# PROB_S7CAS_ADC.net
KiCad netlist of a schematic drawn in Altium Designer
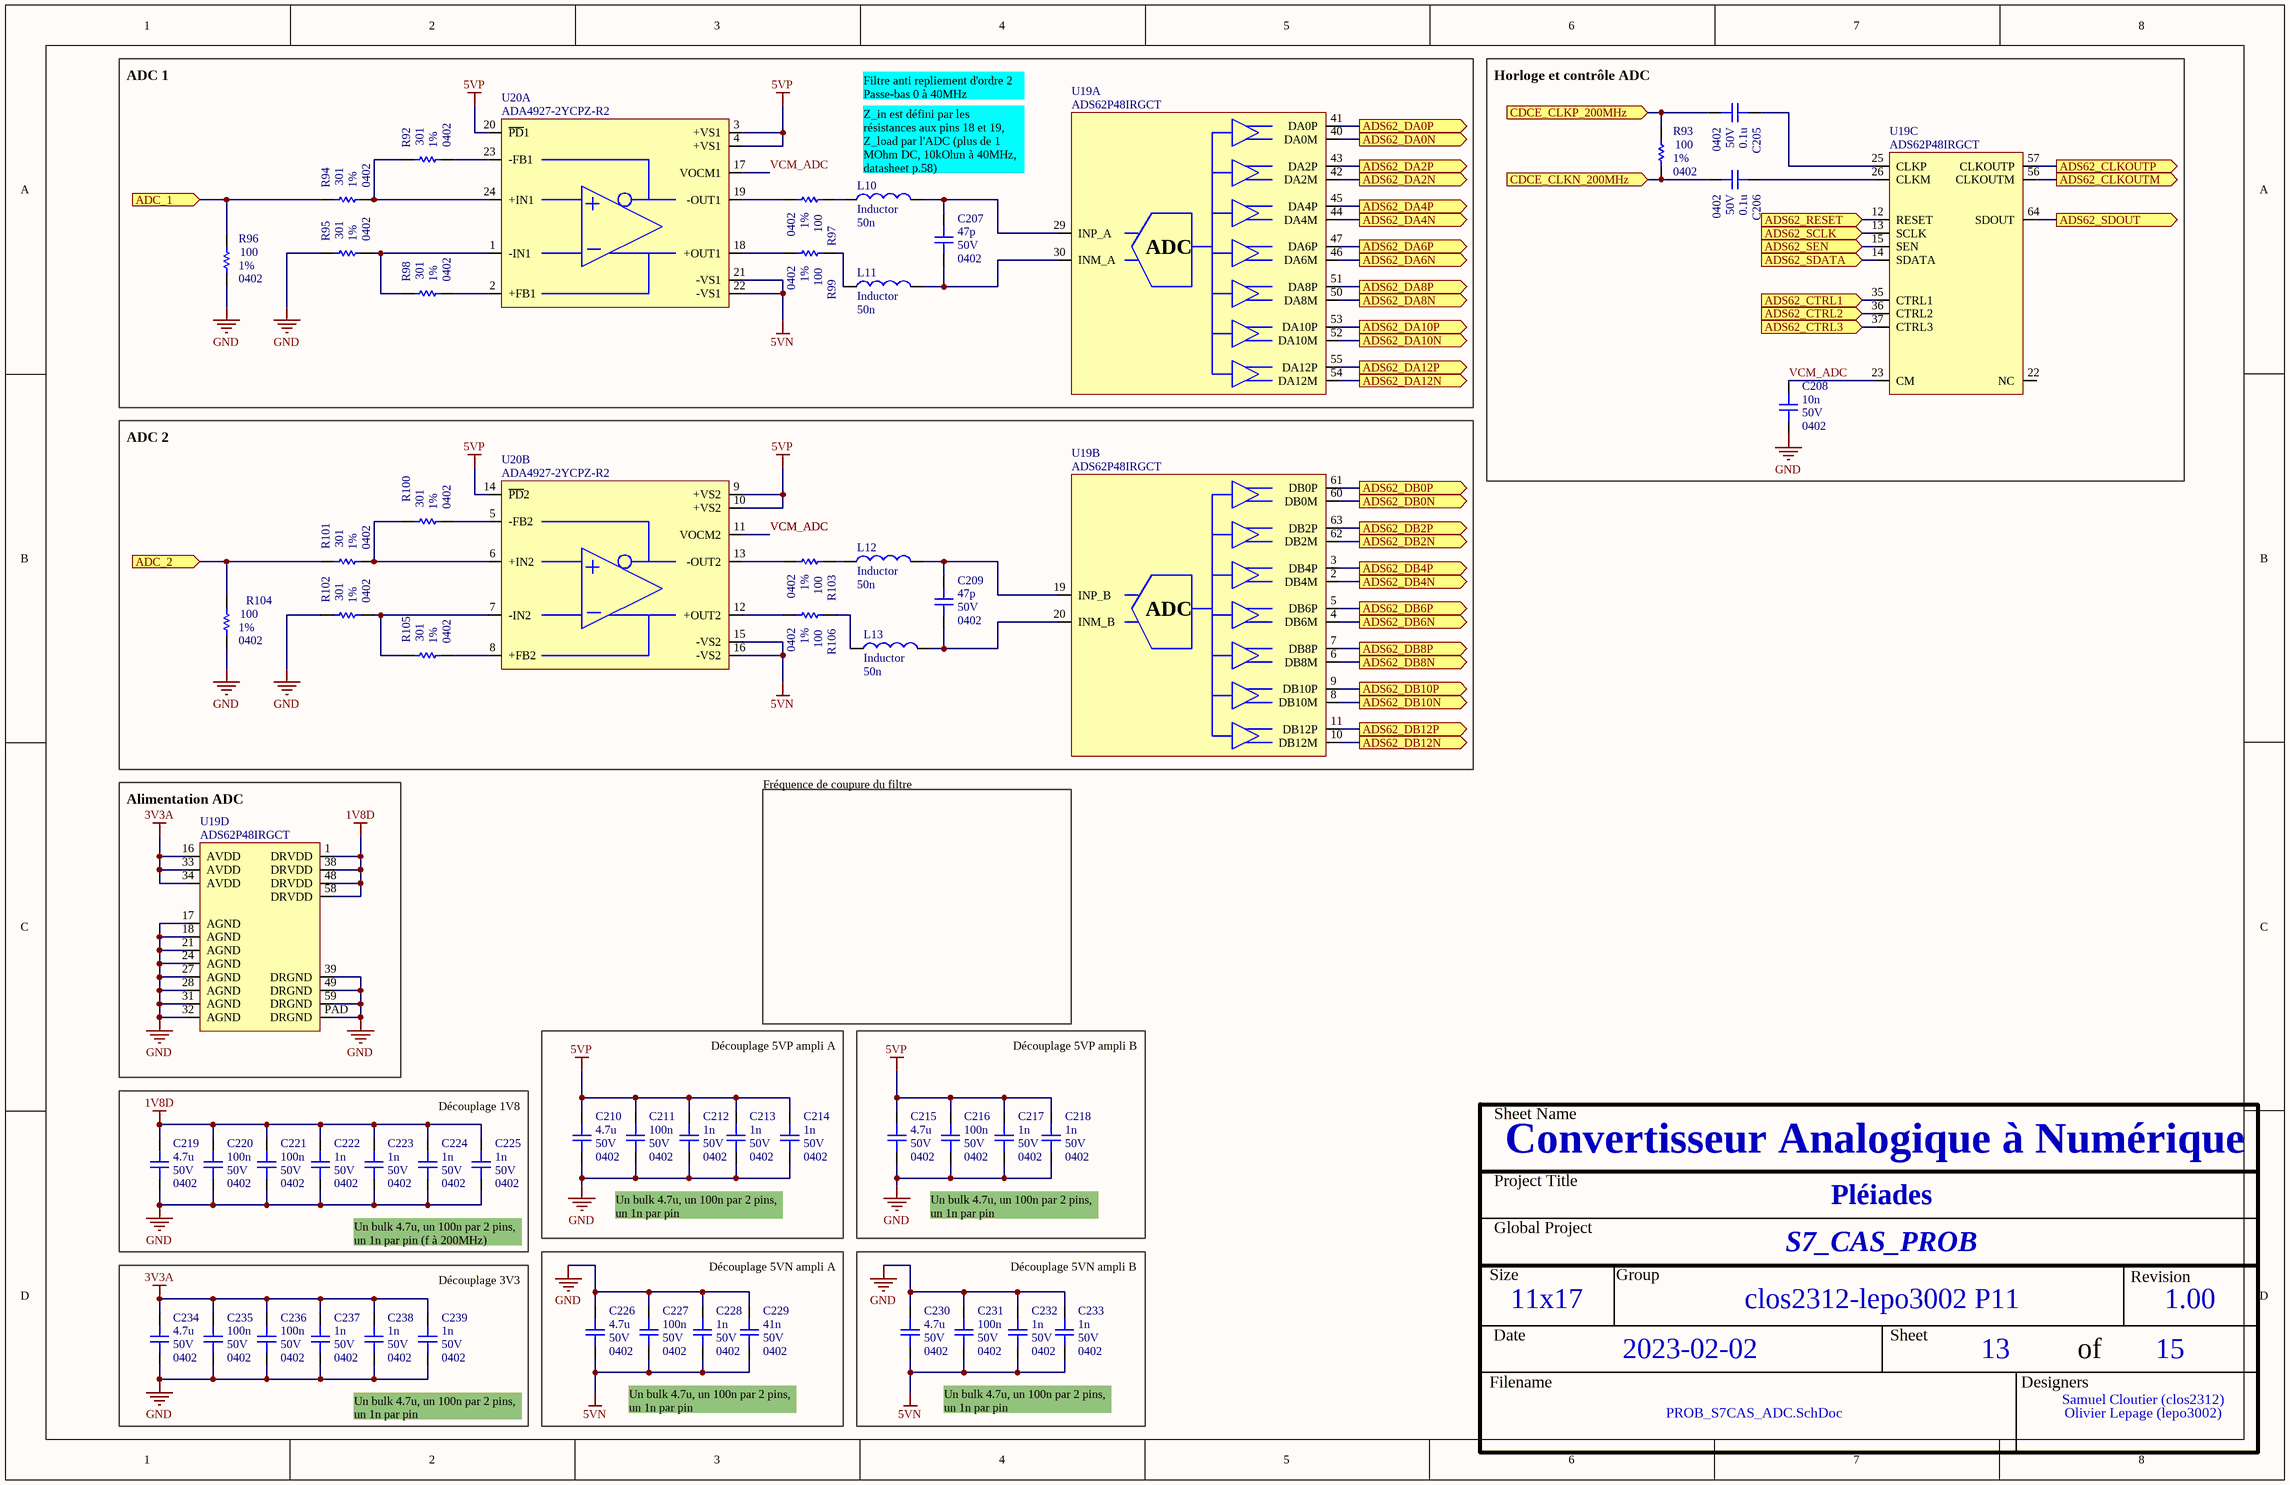
[diagram p0: PROB_S7CAS_ADC.SchDoc]

(export (version "E")
  (design (tool "Eeschema 10.0.6"))
  (components
    (comp (ref "C205")
      (value "0.1u")
      (footprint "CAP_0402")
      (description "CAP - 0402")
      (fields
        (field (name "VOLTAGE") "50V")
        (field (name "PACKAGE") "0402")
        (field (name "CREATEDBY") "Jonathan Bouchard")
      )
      (libsource (lib "S7CAS_LIB2021") (part "CAP - 0402"))
    )
    (comp (ref "C206")
      (value "0.1u")
      (footprint "CAP_0402")
      (description "CAP - 0402")
      (fields
        (field (name "VOLTAGE") "50V")
        (field (name "PACKAGE") "0402")
        (field (name "CREATEDBY") "Jonathan Bouchard")
      )
      (libsource (lib "S7CAS_LIB2021") (part "CAP - 0402"))
    )
    (comp (ref "C207")
      (value "47p")
      (footprint "CAP_0402")
      (description "CAP - 0402")
      (fields
        (field (name "VOLTAGE") "50V")
        (field (name "PACKAGE") "0402")
        (field (name "CREATEDBY") "Jonathan Bouchard")
      )
      (libsource (lib "S7CAS_LIB2021") (part "CAP - 0402"))
    )
    (comp (ref "C208")
      (value "10n")
      (footprint "CAP_0402")
      (description "CAP - 0402")
      (fields
        (field (name "VOLTAGE") "50V")
        (field (name "PACKAGE") "0402")
        (field (name "CREATEDBY") "Jonathan Bouchard")
      )
      (libsource (lib "S7CAS_LIB2021") (part "CAP - 0402"))
    )
    (comp (ref "C209")
      (value "47p")
      (footprint "CAP_0402")
      (description "CAP - 0402")
      (fields
        (field (name "VOLTAGE") "50V")
        (field (name "PACKAGE") "0402")
        (field (name "CREATEDBY") "Jonathan Bouchard")
      )
      (libsource (lib "S7CAS_LIB2021") (part "CAP - 0402"))
    )
    (comp (ref "C210")
      (value "4.7u")
      (footprint "CAP_0402")
      (description "CAP - 0402")
      (fields
        (field (name "VOLTAGE") "50V")
        (field (name "PACKAGE") "0402")
        (field (name "CREATEDBY") "Jonathan Bouchard")
      )
      (libsource (lib "S7CAS_LIB2021") (part "CAP - 0402"))
    )
    (comp (ref "C211")
      (value "100n")
      (footprint "CAP_0402")
      (description "CAP - 0402")
      (fields
        (field (name "VOLTAGE") "50V")
        (field (name "PACKAGE") "0402")
        (field (name "CREATEDBY") "Jonathan Bouchard")
      )
      (libsource (lib "S7CAS_LIB2021") (part "CAP - 0402"))
    )
    (comp (ref "C212")
      (value "1n")
      (footprint "CAP_0402")
      (description "CAP - 0402")
      (fields
        (field (name "VOLTAGE") "50V")
        (field (name "PACKAGE") "0402")
        (field (name "CREATEDBY") "Jonathan Bouchard")
      )
      (libsource (lib "S7CAS_LIB2021") (part "CAP - 0402"))
    )
    (comp (ref "C213")
      (value "1n")
      (footprint "CAP_0402")
      (description "CAP - 0402")
      (fields
        (field (name "VOLTAGE") "50V")
        (field (name "PACKAGE") "0402")
        (field (name "CREATEDBY") "Jonathan Bouchard")
      )
      (libsource (lib "S7CAS_LIB2021") (part "CAP - 0402"))
    )
    (comp (ref "C214")
      (value "1n")
      (footprint "CAP_0402")
      (description "CAP - 0402")
      (fields
        (field (name "VOLTAGE") "50V")
        (field (name "PACKAGE") "0402")
        (field (name "CREATEDBY") "Jonathan Bouchard")
      )
      (libsource (lib "S7CAS_LIB2021") (part "CAP - 0402"))
    )
    (comp (ref "C215")
      (value "4.7u")
      (footprint "CAP_0402")
      (description "CAP - 0402")
      (fields
        (field (name "VOLTAGE") "50V")
        (field (name "PACKAGE") "0402")
        (field (name "CREATEDBY") "Jonathan Bouchard")
      )
      (libsource (lib "S7CAS_LIB2021") (part "CAP - 0402"))
    )
    (comp (ref "C216")
      (value "100n")
      (footprint "CAP_0402")
      (description "CAP - 0402")
      (fields
        (field (name "VOLTAGE") "50V")
        (field (name "PACKAGE") "0402")
        (field (name "CREATEDBY") "Jonathan Bouchard")
      )
      (libsource (lib "S7CAS_LIB2021") (part "CAP - 0402"))
    )
    (comp (ref "C217")
      (value "1n")
      (footprint "CAP_0402")
      (description "CAP - 0402")
      (fields
        (field (name "VOLTAGE") "50V")
        (field (name "PACKAGE") "0402")
        (field (name "CREATEDBY") "Jonathan Bouchard")
      )
      (libsource (lib "S7CAS_LIB2021") (part "CAP - 0402"))
    )
    (comp (ref "C218")
      (value "1n")
      (footprint "CAP_0402")
      (description "CAP - 0402")
      (fields
        (field (name "VOLTAGE") "50V")
        (field (name "PACKAGE") "0402")
        (field (name "CREATEDBY") "Jonathan Bouchard")
      )
      (libsource (lib "S7CAS_LIB2021") (part "CAP - 0402"))
    )
    (comp (ref "C219")
      (value "4.7u")
      (footprint "CAP_0402")
      (description "CAP - 0402")
      (fields
        (field (name "VOLTAGE") "50V")
        (field (name "PACKAGE") "0402")
        (field (name "CREATEDBY") "Jonathan Bouchard")
      )
      (libsource (lib "S7CAS_LIB2021") (part "CAP - 0402"))
    )
    (comp (ref "C220")
      (value "100n")
      (footprint "CAP_0402")
      (description "CAP - 0402")
      (fields
        (field (name "VOLTAGE") "50V")
        (field (name "PACKAGE") "0402")
        (field (name "CREATEDBY") "Jonathan Bouchard")
      )
      (libsource (lib "S7CAS_LIB2021") (part "CAP - 0402"))
    )
    (comp (ref "C221")
      (value "100n")
      (footprint "CAP_0402")
      (description "CAP - 0402")
      (fields
        (field (name "VOLTAGE") "50V")
        (field (name "PACKAGE") "0402")
        (field (name "CREATEDBY") "Jonathan Bouchard")
      )
      (libsource (lib "S7CAS_LIB2021") (part "CAP - 0402"))
    )
    (comp (ref "C222")
      (value "1n")
      (footprint "CAP_0402")
      (description "CAP - 0402")
      (fields
        (field (name "VOLTAGE") "50V")
        (field (name "PACKAGE") "0402")
        (field (name "CREATEDBY") "Jonathan Bouchard")
      )
      (libsource (lib "S7CAS_LIB2021") (part "CAP - 0402"))
    )
    (comp (ref "C223")
      (value "1n")
      (footprint "CAP_0402")
      (description "CAP - 0402")
      (fields
        (field (name "VOLTAGE") "50V")
        (field (name "PACKAGE") "0402")
        (field (name "CREATEDBY") "Jonathan Bouchard")
      )
      (libsource (lib "S7CAS_LIB2021") (part "CAP - 0402"))
    )
    (comp (ref "C224")
      (value "1n")
      (footprint "CAP_0402")
      (description "CAP - 0402")
      (fields
        (field (name "VOLTAGE") "50V")
        (field (name "PACKAGE") "0402")
        (field (name "CREATEDBY") "Jonathan Bouchard")
      )
      (libsource (lib "S7CAS_LIB2021") (part "CAP - 0402"))
    )
    (comp (ref "C225")
      (value "1n")
      (footprint "CAP_0402")
      (description "CAP - 0402")
      (fields
        (field (name "VOLTAGE") "50V")
        (field (name "PACKAGE") "0402")
        (field (name "CREATEDBY") "Jonathan Bouchard")
      )
      (libsource (lib "S7CAS_LIB2021") (part "CAP - 0402"))
    )
    (comp (ref "C226")
      (value "4.7u")
      (footprint "CAP_0402")
      (description "CAP - 0402")
      (fields
        (field (name "VOLTAGE") "50V")
        (field (name "PACKAGE") "0402")
        (field (name "CREATEDBY") "Jonathan Bouchard")
      )
      (libsource (lib "S7CAS_LIB2021") (part "CAP - 0402"))
    )
    (comp (ref "C227")
      (value "100n")
      (footprint "CAP_0402")
      (description "CAP - 0402")
      (fields
        (field (name "VOLTAGE") "50V")
        (field (name "PACKAGE") "0402")
        (field (name "CREATEDBY") "Jonathan Bouchard")
      )
      (libsource (lib "S7CAS_LIB2021") (part "CAP - 0402"))
    )
    (comp (ref "C228")
      (value "1n")
      (footprint "CAP_0402")
      (description "CAP - 0402")
      (fields
        (field (name "VOLTAGE") "50V")
        (field (name "PACKAGE") "0402")
        (field (name "CREATEDBY") "Jonathan Bouchard")
      )
      (libsource (lib "S7CAS_LIB2021") (part "CAP - 0402"))
    )
    (comp (ref "C229")
      (value "41n")
      (footprint "CAP_0402")
      (description "CAP - 0402")
      (fields
        (field (name "VOLTAGE") "50V")
        (field (name "PACKAGE") "0402")
        (field (name "CREATEDBY") "Jonathan Bouchard")
      )
      (libsource (lib "S7CAS_LIB2021") (part "CAP - 0402"))
    )
    (comp (ref "C230")
      (value "4.7u")
      (footprint "CAP_0402")
      (description "CAP - 0402")
      (fields
        (field (name "VOLTAGE") "50V")
        (field (name "PACKAGE") "0402")
        (field (name "CREATEDBY") "Jonathan Bouchard")
      )
      (libsource (lib "S7CAS_LIB2021") (part "CAP - 0402"))
    )
    (comp (ref "C231")
      (value "100n")
      (footprint "CAP_0402")
      (description "CAP - 0402")
      (fields
        (field (name "VOLTAGE") "50V")
        (field (name "PACKAGE") "0402")
        (field (name "CREATEDBY") "Jonathan Bouchard")
      )
      (libsource (lib "S7CAS_LIB2021") (part "CAP - 0402"))
    )
    (comp (ref "C232")
      (value "1n")
      (footprint "CAP_0402")
      (description "CAP - 0402")
      (fields
        (field (name "VOLTAGE") "50V")
        (field (name "PACKAGE") "0402")
        (field (name "CREATEDBY") "Jonathan Bouchard")
      )
      (libsource (lib "S7CAS_LIB2021") (part "CAP - 0402"))
    )
    (comp (ref "C233")
      (value "1n")
      (footprint "CAP_0402")
      (description "CAP - 0402")
      (fields
        (field (name "VOLTAGE") "50V")
        (field (name "PACKAGE") "0402")
        (field (name "CREATEDBY") "Jonathan Bouchard")
      )
      (libsource (lib "S7CAS_LIB2021") (part "CAP - 0402"))
    )
    (comp (ref "C234")
      (value "4.7u")
      (footprint "CAP_0402")
      (description "CAP - 0402")
      (fields
        (field (name "VOLTAGE") "50V")
        (field (name "PACKAGE") "0402")
        (field (name "CREATEDBY") "Jonathan Bouchard")
      )
      (libsource (lib "S7CAS_LIB2021") (part "CAP - 0402"))
    )
    (comp (ref "C235")
      (value "100n")
      (footprint "CAP_0402")
      (description "CAP - 0402")
      (fields
        (field (name "VOLTAGE") "50V")
        (field (name "PACKAGE") "0402")
        (field (name "CREATEDBY") "Jonathan Bouchard")
      )
      (libsource (lib "S7CAS_LIB2021") (part "CAP - 0402"))
    )
    (comp (ref "C236")
      (value "100n")
      (footprint "CAP_0402")
      (description "CAP - 0402")
      (fields
        (field (name "VOLTAGE") "50V")
        (field (name "PACKAGE") "0402")
        (field (name "CREATEDBY") "Jonathan Bouchard")
      )
      (libsource (lib "S7CAS_LIB2021") (part "CAP - 0402"))
    )
    (comp (ref "C237")
      (value "1n")
      (footprint "CAP_0402")
      (description "CAP - 0402")
      (fields
        (field (name "VOLTAGE") "50V")
        (field (name "PACKAGE") "0402")
        (field (name "CREATEDBY") "Jonathan Bouchard")
      )
      (libsource (lib "S7CAS_LIB2021") (part "CAP - 0402"))
    )
    (comp (ref "C238")
      (value "1n")
      (footprint "CAP_0402")
      (description "CAP - 0402")
      (fields
        (field (name "VOLTAGE") "50V")
        (field (name "PACKAGE") "0402")
        (field (name "CREATEDBY") "Jonathan Bouchard")
      )
      (libsource (lib "S7CAS_LIB2021") (part "CAP - 0402"))
    )
    (comp (ref "C239")
      (value "1n")
      (footprint "CAP_0402")
      (description "CAP - 0402")
      (fields
        (field (name "VOLTAGE") "50V")
        (field (name "PACKAGE") "0402")
        (field (name "CREATEDBY") "Jonathan Bouchard")
      )
      (libsource (lib "S7CAS_LIB2021") (part "CAP - 0402"))
    )
    (comp (ref "L10")
      (value "Inductor")
      (footprint "INDM5250X66N")
      (description "IND PWR BEAD 50NH 48A SMD")
      (fields (field (name "ALTIUM_VALUE") "50n"))
      (libsource (lib "LIB_TEMP_S7CAS_SCH") (part "Inductor"))
    )
    (comp (ref "L11")
      (value "Inductor")
      (footprint "INDM5250X66N")
      (description "IND PWR BEAD 50NH 48A SMD")
      (fields (field (name "ALTIUM_VALUE") "50n"))
      (libsource (lib "LIB_TEMP_S7CAS_SCH") (part "Inductor"))
    )
    (comp (ref "L12")
      (value "Inductor")
      (footprint "INDM5250X66N")
      (description "IND PWR BEAD 50NH 48A SMD")
      (fields (field (name "ALTIUM_VALUE") "50n"))
      (libsource (lib "LIB_TEMP_S7CAS_SCH") (part "Inductor"))
    )
    (comp (ref "L13")
      (value "Inductor")
      (footprint "INDM5250X66N")
      (description "IND PWR BEAD 50NH 48A SMD")
      (fields (field (name "ALTIUM_VALUE") "50n"))
      (libsource (lib "LIB_TEMP_S7CAS_SCH") (part "Inductor"))
    )
    (comp (ref "R92")
      (value "301")
      (footprint "RES_0402")
      (description "RES - 0402")
      (fields
        (field (name "VOLTAGE") "50V")
        (field (name "POWER") "1/16W")
        (field (name "PACKAGE") "0402")
        (field (name "PRECISION") "1%")
        (field (name "CREATEDBY") "Jonathan Bouchard")
      )
      (libsource (lib "S7CAS_LIB2021") (part "RES - 0402"))
    )
    (comp (ref "R93")
      (value "100")
      (footprint "RES_0402")
      (description "RES - 0402")
      (fields
        (field (name "VOLTAGE") "50V")
        (field (name "POWER") "1/16W")
        (field (name "PACKAGE") "0402")
        (field (name "PRECISION") "1%")
        (field (name "CREATEDBY") "Jonathan Bouchard")
      )
      (libsource (lib "S7CAS_LIB2021") (part "RES - 0402"))
    )
    (comp (ref "R94")
      (value "301")
      (footprint "RES_0402")
      (description "RES - 0402")
      (fields
        (field (name "VOLTAGE") "50V")
        (field (name "POWER") "1/16W")
        (field (name "PACKAGE") "0402")
        (field (name "PRECISION") "1%")
        (field (name "CREATEDBY") "Jonathan Bouchard")
      )
      (libsource (lib "S7CAS_LIB2021") (part "RES - 0402"))
    )
    (comp (ref "R95")
      (value "301")
      (footprint "RES_0402")
      (description "RES - 0402")
      (fields
        (field (name "VOLTAGE") "50V")
        (field (name "POWER") "1/16W")
        (field (name "PACKAGE") "0402")
        (field (name "PRECISION") "1%")
        (field (name "CREATEDBY") "Jonathan Bouchard")
      )
      (libsource (lib "S7CAS_LIB2021") (part "RES - 0402"))
    )
    (comp (ref "R96")
      (value "100")
      (footprint "RES_0402")
      (description "RES - 0402")
      (fields
        (field (name "VOLTAGE") "50V")
        (field (name "POWER") "1/16W")
        (field (name "PACKAGE") "0402")
        (field (name "PRECISION") "1%")
        (field (name "CREATEDBY") "Jonathan Bouchard")
      )
      (libsource (lib "S7CAS_LIB2021") (part "RES - 0402"))
    )
    (comp (ref "R97")
      (value "100")
      (footprint "RES_0402")
      (description "RES - 0402")
      (fields
        (field (name "VOLTAGE") "50V")
        (field (name "POWER") "1/16W")
        (field (name "PACKAGE") "0402")
        (field (name "PRECISION") "1%")
        (field (name "CREATEDBY") "Jonathan Bouchard")
      )
      (libsource (lib "S7CAS_LIB2021") (part "RES - 0402"))
    )
    (comp (ref "R98")
      (value "301")
      (footprint "RES_0402")
      (description "RES - 0402")
      (fields
        (field (name "VOLTAGE") "50V")
        (field (name "POWER") "1/16W")
        (field (name "PACKAGE") "0402")
        (field (name "PRECISION") "1%")
        (field (name "CREATEDBY") "Jonathan Bouchard")
      )
      (libsource (lib "S7CAS_LIB2021") (part "RES - 0402"))
    )
    (comp (ref "R99")
      (value "100")
      (footprint "RES_0402")
      (description "RES - 0402")
      (fields
        (field (name "VOLTAGE") "50V")
        (field (name "POWER") "1/16W")
        (field (name "PACKAGE") "0402")
        (field (name "PRECISION") "1%")
        (field (name "CREATEDBY") "Jonathan Bouchard")
      )
      (libsource (lib "S7CAS_LIB2021") (part "RES - 0402"))
    )
    (comp (ref "R100")
      (value "301")
      (footprint "RES_0402")
      (description "RES - 0402")
      (fields
        (field (name "VOLTAGE") "50V")
        (field (name "POWER") "1/16W")
        (field (name "PACKAGE") "0402")
        (field (name "PRECISION") "1%")
        (field (name "CREATEDBY") "Jonathan Bouchard")
      )
      (libsource (lib "S7CAS_LIB2021") (part "RES - 0402"))
    )
    (comp (ref "R101")
      (value "301")
      (footprint "RES_0402")
      (description "RES - 0402")
      (fields
        (field (name "VOLTAGE") "50V")
        (field (name "POWER") "1/16W")
        (field (name "PACKAGE") "0402")
        (field (name "PRECISION") "1%")
        (field (name "CREATEDBY") "Jonathan Bouchard")
      )
      (libsource (lib "S7CAS_LIB2021") (part "RES - 0402"))
    )
    (comp (ref "R102")
      (value "301")
      (footprint "RES_0402")
      (description "RES - 0402")
      (fields
        (field (name "VOLTAGE") "50V")
        (field (name "POWER") "1/16W")
        (field (name "PACKAGE") "0402")
        (field (name "PRECISION") "1%")
        (field (name "CREATEDBY") "Jonathan Bouchard")
      )
      (libsource (lib "S7CAS_LIB2021") (part "RES - 0402"))
    )
    (comp (ref "R103")
      (value "100")
      (footprint "RES_0402")
      (description "RES - 0402")
      (fields
        (field (name "VOLTAGE") "50V")
        (field (name "POWER") "1/16W")
        (field (name "PACKAGE") "0402")
        (field (name "PRECISION") "1%")
        (field (name "CREATEDBY") "Jonathan Bouchard")
      )
      (libsource (lib "S7CAS_LIB2021") (part "RES - 0402"))
    )
    (comp (ref "R104")
      (value "100")
      (footprint "RES_0402")
      (description "RES - 0402")
      (fields
        (field (name "VOLTAGE") "50V")
        (field (name "POWER") "1/16W")
        (field (name "PACKAGE") "0402")
        (field (name "PRECISION") "1%")
        (field (name "CREATEDBY") "Jonathan Bouchard")
      )
      (libsource (lib "S7CAS_LIB2021") (part "RES - 0402"))
    )
    (comp (ref "R105")
      (value "301")
      (footprint "RES_0402")
      (description "RES - 0402")
      (fields
        (field (name "VOLTAGE") "50V")
        (field (name "POWER") "1/16W")
        (field (name "PACKAGE") "0402")
        (field (name "PRECISION") "1%")
        (field (name "CREATEDBY") "Jonathan Bouchard")
      )
      (libsource (lib "S7CAS_LIB2021") (part "RES - 0402"))
    )
    (comp (ref "R106")
      (value "100")
      (footprint "RES_0402")
      (description "RES - 0402")
      (fields
        (field (name "VOLTAGE") "50V")
        (field (name "POWER") "1/16W")
        (field (name "PACKAGE") "0402")
        (field (name "PRECISION") "1%")
        (field (name "CREATEDBY") "Jonathan Bouchard")
      )
      (libsource (lib "S7CAS_LIB2021") (part "RES - 0402"))
    )
    (comp (ref "U19")
      (value "ADS62P48IRGCT")
      (footprint "ADC_ADS62P48IRGCT")
      (description "ADC - 14 BIT 210MSPS SUAL - VQFN-64")
      (fields
        (field (name "VOLTAGE") "3.15 V ~ 3.6 V / 1.7 V ~ 1.9 V")
        (field (name "MFG") "Texas Instruments")
        (field (name "CREATEDBY") "Jonathan Bouchard")
      )
      (libsource (lib "S7CAS_LIB2021") (part "ADC_ADS62P48IRGCT"))
    )
    (comp (ref "U20")
      (value "ADA4927-2YCPZ-R2")
      (footprint "OPAMP_ADA4927-2YCPZ-R2")
      (description "OPAMP - CFA 2.3GHZ - QFN-24")
      (fields
        (field (name "VOLTAGE") "4.5 V ~ 11 V, ±2.25 V ~ 5.5 V")
        (field (name "MFG") "Analog Devices")
        (field (name "CREATEDBY") "Jonathan Bouchard")
      )
      (libsource (lib "S7CAS_LIB2021") (part "OPAMP_ADA4927-2YCPZ-R2"))
    )
  )
  (nets
    (net (code "1") (name "/ADC_1") (class "Default")
      (node (ref "R94") (pin "2") (pinfunction "2_2") (pintype "passive"))
      (node (ref "R96") (pin "2") (pinfunction "2_2") (pintype "passive"))
    )
    (net (code "2") (name "/ADC_2") (class "Default")
      (node (ref "R101") (pin "2") (pinfunction "2_2") (pintype "passive"))
      (node (ref "R104") (pin "2") (pinfunction "2_2") (pintype "passive"))
    )
    (net (code "3") (name "/ADS62_CLKOUTM") (class "Default")
      (node (ref "U19") (pin "56") (pinfunction "CLKOUTM_56") (pintype "passive"))
    )
    (net (code "4") (name "/ADS62_CLKOUTP") (class "Default")
      (node (ref "U19") (pin "57") (pinfunction "CLKOUTP_57") (pintype "passive"))
    )
    (net (code "5") (name "/ADS62_CTRL1") (class "Default")
      (node (ref "U19") (pin "35") (pinfunction "CTRL1_35") (pintype "passive"))
    )
    (net (code "6") (name "/ADS62_CTRL2") (class "Default")
      (node (ref "U19") (pin "36") (pinfunction "CTRL2_36") (pintype "passive"))
    )
    (net (code "7") (name "/ADS62_CTRL3") (class "Default")
      (node (ref "U19") (pin "37") (pinfunction "CTRL3_37") (pintype "passive"))
    )
    (net (code "8") (name "/ADS62_DA0N") (class "Default")
      (node (ref "U19") (pin "40") (pinfunction "DA0M_40") (pintype "passive"))
    )
    (net (code "9") (name "/ADS62_DA0P") (class "Default")
      (node (ref "U19") (pin "41") (pinfunction "DA0P_41") (pintype "passive"))
    )
    (net (code "10") (name "/ADS62_DA2N") (class "Default")
      (node (ref "U19") (pin "42") (pinfunction "DA2M_42") (pintype "passive"))
    )
    (net (code "11") (name "/ADS62_DA2P") (class "Default")
      (node (ref "U19") (pin "43") (pinfunction "DA2P_43") (pintype "passive"))
    )
    (net (code "12") (name "/ADS62_DA4N") (class "Default")
      (node (ref "U19") (pin "44") (pinfunction "DA4M_44") (pintype "passive"))
    )
    (net (code "13") (name "/ADS62_DA4P") (class "Default")
      (node (ref "U19") (pin "45") (pinfunction "DA4P_45") (pintype "passive"))
    )
    (net (code "14") (name "/ADS62_DA6N") (class "Default")
      (node (ref "U19") (pin "46") (pinfunction "DA6M_46") (pintype "passive"))
    )
    (net (code "15") (name "/ADS62_DA6P") (class "Default")
      (node (ref "U19") (pin "47") (pinfunction "DA6P_47") (pintype "passive"))
    )
    (net (code "16") (name "/ADS62_DA8N") (class "Default")
      (node (ref "U19") (pin "50") (pinfunction "DA8M_50") (pintype "passive"))
    )
    (net (code "17") (name "/ADS62_DA8P") (class "Default")
      (node (ref "U19") (pin "51") (pinfunction "DA8P_51") (pintype "passive"))
    )
    (net (code "18") (name "/ADS62_DA10N") (class "Default")
      (node (ref "U19") (pin "52") (pinfunction "DA10M_52") (pintype "passive"))
    )
    (net (code "19") (name "/ADS62_DA10P") (class "Default")
      (node (ref "U19") (pin "53") (pinfunction "DA10P_53") (pintype "passive"))
    )
    (net (code "20") (name "/ADS62_DA12N") (class "Default")
      (node (ref "U19") (pin "54") (pinfunction "DA12M_54") (pintype "passive"))
    )
    (net (code "21") (name "/ADS62_DA12P") (class "Default")
      (node (ref "U19") (pin "55") (pinfunction "DA12P_55") (pintype "passive"))
    )
    (net (code "22") (name "/ADS62_DB0N") (class "Default")
      (node (ref "U19") (pin "60") (pinfunction "DB0M_60") (pintype "passive"))
    )
    (net (code "23") (name "/ADS62_DB0P") (class "Default")
      (node (ref "U19") (pin "61") (pinfunction "DB0P_61") (pintype "passive"))
    )
    (net (code "24") (name "/ADS62_DB2N") (class "Default")
      (node (ref "U19") (pin "62") (pinfunction "DB2M_62") (pintype "passive"))
    )
    (net (code "25") (name "/ADS62_DB2P") (class "Default")
      (node (ref "U19") (pin "63") (pinfunction "DB2P_63") (pintype "passive"))
    )
    (net (code "26") (name "/ADS62_DB4N") (class "Default")
      (node (ref "U19") (pin "2") (pinfunction "DB4M_2") (pintype "passive"))
    )
    (net (code "27") (name "/ADS62_DB4P") (class "Default")
      (node (ref "U19") (pin "3") (pinfunction "DB4P_3") (pintype "passive"))
    )
    (net (code "28") (name "/ADS62_DB6N") (class "Default")
      (node (ref "U19") (pin "4") (pinfunction "DB6M_4") (pintype "passive"))
    )
    (net (code "29") (name "/ADS62_DB6P") (class "Default")
      (node (ref "U19") (pin "5") (pinfunction "DB6P_5") (pintype "passive"))
    )
    (net (code "30") (name "/ADS62_DB8N") (class "Default")
      (node (ref "U19") (pin "6") (pinfunction "DB8M_6") (pintype "passive"))
    )
    (net (code "31") (name "/ADS62_DB8P") (class "Default")
      (node (ref "U19") (pin "7") (pinfunction "DB8P_7") (pintype "passive"))
    )
    (net (code "32") (name "/ADS62_DB10N") (class "Default")
      (node (ref "U19") (pin "8") (pinfunction "DB10M_8") (pintype "passive"))
    )
    (net (code "33") (name "/ADS62_DB10P") (class "Default")
      (node (ref "U19") (pin "9") (pinfunction "DB10P_9") (pintype "passive"))
    )
    (net (code "34") (name "/ADS62_DB12N") (class "Default")
      (node (ref "U19") (pin "10") (pinfunction "DB12M_10") (pintype "passive"))
    )
    (net (code "35") (name "/ADS62_DB12P") (class "Default")
      (node (ref "U19") (pin "11") (pinfunction "DB12P_11") (pintype "passive"))
    )
    (net (code "36") (name "/ADS62_RESET") (class "Default")
      (node (ref "U19") (pin "12") (pinfunction "RESET_12") (pintype "passive"))
    )
    (net (code "37") (name "/ADS62_SCLK") (class "Default")
      (node (ref "U19") (pin "13") (pinfunction "SCLK_13") (pintype "passive"))
    )
    (net (code "38") (name "/ADS62_SDATA") (class "Default")
      (node (ref "U19") (pin "14") (pinfunction "SDATA_14") (pintype "passive"))
    )
    (net (code "39") (name "/ADS62_SDOUT") (class "Default")
      (node (ref "U19") (pin "64") (pinfunction "SDOUT_64") (pintype "passive"))
    )
    (net (code "40") (name "/ADS62_SEN") (class "Default")
      (node (ref "U19") (pin "15") (pinfunction "SEN_15") (pintype "passive"))
    )
    (net (code "41") (name "/CDCE_CLKN_200MHz") (class "Default")
      (node (ref "C206") (pin "1") (pinfunction "1_1") (pintype "passive"))
      (node (ref "R93") (pin "1") (pinfunction "1_1") (pintype "passive"))
    )
    (net (code "42") (name "/CDCE_CLKP_200MHz") (class "Default")
      (node (ref "C205") (pin "1") (pinfunction "1_1") (pintype "passive"))
      (node (ref "R93") (pin "2") (pinfunction "2_2") (pintype "passive"))
    )
    (net (code "43") (name "/VCM_ADC") (class "Default")
      (node (ref "C208") (pin "2") (pinfunction "2_2") (pintype "passive"))
      (node (ref "U19") (pin "23") (pinfunction "CM_23") (pintype "passive"))
      (node (ref "U20") (pin "11") (pinfunction "VOCM2_11") (pintype "passive"))
      (node (ref "U20") (pin "17") (pinfunction "VOCM1_17") (pintype "passive"))
    )
    (net (code "44") (name "1V8D") (class "Default")
      (node (ref "C219") (pin "2") (pinfunction "2_2") (pintype "passive"))
      (node (ref "C220") (pin "2") (pinfunction "2_2") (pintype "passive"))
      (node (ref "C221") (pin "2") (pinfunction "2_2") (pintype "passive"))
      (node (ref "C222") (pin "2") (pinfunction "2_2") (pintype "passive"))
      (node (ref "C223") (pin "2") (pinfunction "2_2") (pintype "passive"))
      (node (ref "C224") (pin "2") (pinfunction "2_2") (pintype "passive"))
      (node (ref "C225") (pin "2") (pinfunction "2_2") (pintype "passive"))
      (node (ref "U19") (pin "1") (pinfunction "DRVDD_1") (pintype "passive"))
      (node (ref "U19") (pin "38") (pinfunction "DRVDD_38") (pintype "passive"))
      (node (ref "U19") (pin "48") (pinfunction "DRVDD_48") (pintype "passive"))
      (node (ref "U19") (pin "58") (pinfunction "DRVDD_58") (pintype "passive"))
    )
    (net (code "45") (name "3V3A") (class "Default")
      (node (ref "C234") (pin "2") (pinfunction "2_2") (pintype "passive"))
      (node (ref "C235") (pin "2") (pinfunction "2_2") (pintype "passive"))
      (node (ref "C236") (pin "2") (pinfunction "2_2") (pintype "passive"))
      (node (ref "C237") (pin "2") (pinfunction "2_2") (pintype "passive"))
      (node (ref "C238") (pin "2") (pinfunction "2_2") (pintype "passive"))
      (node (ref "C239") (pin "2") (pinfunction "2_2") (pintype "passive"))
      (node (ref "U19") (pin "16") (pinfunction "AVDD_16") (pintype "passive"))
      (node (ref "U19") (pin "33") (pinfunction "AVDD_33") (pintype "passive"))
      (node (ref "U19") (pin "34") (pinfunction "AVDD_34") (pintype "passive"))
    )
    (net (code "46") (name "5VN") (class "Default")
      (node (ref "C226") (pin "1") (pinfunction "1_1") (pintype "passive"))
      (node (ref "C227") (pin "1") (pinfunction "1_1") (pintype "passive"))
      (node (ref "C228") (pin "1") (pinfunction "1_1") (pintype "passive"))
      (node (ref "C229") (pin "1") (pinfunction "1_1") (pintype "passive"))
      (node (ref "C230") (pin "1") (pinfunction "1_1") (pintype "passive"))
      (node (ref "C231") (pin "1") (pinfunction "1_1") (pintype "passive"))
      (node (ref "C232") (pin "1") (pinfunction "1_1") (pintype "passive"))
      (node (ref "C233") (pin "1") (pinfunction "1_1") (pintype "passive"))
      (node (ref "U20") (pin "15") (pinfunction "-VS2_15") (pintype "passive"))
      (node (ref "U20") (pin "16") (pinfunction "-VS2_16") (pintype "passive"))
      (node (ref "U20") (pin "21") (pinfunction "-VS1_21") (pintype "passive"))
      (node (ref "U20") (pin "22") (pinfunction "-VS1_22") (pintype "passive"))
    )
    (net (code "47") (name "5VP") (class "Default")
      (node (ref "C210") (pin "2") (pinfunction "2_2") (pintype "passive"))
      (node (ref "C211") (pin "2") (pinfunction "2_2") (pintype "passive"))
      (node (ref "C212") (pin "2") (pinfunction "2_2") (pintype "passive"))
      (node (ref "C213") (pin "2") (pinfunction "2_2") (pintype "passive"))
      (node (ref "C214") (pin "2") (pinfunction "2_2") (pintype "passive"))
      (node (ref "C215") (pin "2") (pinfunction "2_2") (pintype "passive"))
      (node (ref "C216") (pin "2") (pinfunction "2_2") (pintype "passive"))
      (node (ref "C217") (pin "2") (pinfunction "2_2") (pintype "passive"))
      (node (ref "C218") (pin "2") (pinfunction "2_2") (pintype "passive"))
      (node (ref "U20") (pin "10") (pinfunction "+VS2_10") (pintype "passive"))
      (node (ref "U20") (pin "14") (pinfunction "~{PD}2_14") (pintype "passive"))
      (node (ref "U20") (pin "20") (pinfunction "~{PD}1_20") (pintype "passive"))
      (node (ref "U20") (pin "3") (pinfunction "+VS1_3") (pintype "passive"))
      (node (ref "U20") (pin "4") (pinfunction "+VS1_4") (pintype "passive"))
      (node (ref "U20") (pin "9") (pinfunction "+VS2_9") (pintype "passive"))
    )
    (net (code "48") (name "GND") (class "Default")
      (node (ref "C208") (pin "1") (pinfunction "1_1") (pintype "passive"))
      (node (ref "C210") (pin "1") (pinfunction "1_1") (pintype "passive"))
      (node (ref "C211") (pin "1") (pinfunction "1_1") (pintype "passive"))
      (node (ref "C212") (pin "1") (pinfunction "1_1") (pintype "passive"))
      (node (ref "C213") (pin "1") (pinfunction "1_1") (pintype "passive"))
      (node (ref "C214") (pin "1") (pinfunction "1_1") (pintype "passive"))
      (node (ref "C215") (pin "1") (pinfunction "1_1") (pintype "passive"))
      (node (ref "C216") (pin "1") (pinfunction "1_1") (pintype "passive"))
      (node (ref "C217") (pin "1") (pinfunction "1_1") (pintype "passive"))
      (node (ref "C218") (pin "1") (pinfunction "1_1") (pintype "passive"))
      (node (ref "C219") (pin "1") (pinfunction "1_1") (pintype "passive"))
      (node (ref "C220") (pin "1") (pinfunction "1_1") (pintype "passive"))
      (node (ref "C221") (pin "1") (pinfunction "1_1") (pintype "passive"))
      (node (ref "C222") (pin "1") (pinfunction "1_1") (pintype "passive"))
      (node (ref "C223") (pin "1") (pinfunction "1_1") (pintype "passive"))
      (node (ref "C224") (pin "1") (pinfunction "1_1") (pintype "passive"))
      (node (ref "C225") (pin "1") (pinfunction "1_1") (pintype "passive"))
      (node (ref "C226") (pin "2") (pinfunction "2_2") (pintype "passive"))
      (node (ref "C227") (pin "2") (pinfunction "2_2") (pintype "passive"))
      (node (ref "C228") (pin "2") (pinfunction "2_2") (pintype "passive"))
      (node (ref "C229") (pin "2") (pinfunction "2_2") (pintype "passive"))
      (node (ref "C230") (pin "2") (pinfunction "2_2") (pintype "passive"))
      (node (ref "C231") (pin "2") (pinfunction "2_2") (pintype "passive"))
      (node (ref "C232") (pin "2") (pinfunction "2_2") (pintype "passive"))
      (node (ref "C233") (pin "2") (pinfunction "2_2") (pintype "passive"))
      (node (ref "C234") (pin "1") (pinfunction "1_1") (pintype "passive"))
      (node (ref "C235") (pin "1") (pinfunction "1_1") (pintype "passive"))
      (node (ref "C236") (pin "1") (pinfunction "1_1") (pintype "passive"))
      (node (ref "C237") (pin "1") (pinfunction "1_1") (pintype "passive"))
      (node (ref "C238") (pin "1") (pinfunction "1_1") (pintype "passive"))
      (node (ref "C239") (pin "1") (pinfunction "1_1") (pintype "passive"))
      (node (ref "R102") (pin "2") (pinfunction "2_2") (pintype "passive"))
      (node (ref "R104") (pin "1") (pinfunction "1_1") (pintype "passive"))
      (node (ref "R95") (pin "2") (pinfunction "2_2") (pintype "passive"))
      (node (ref "R96") (pin "1") (pinfunction "1_1") (pintype "passive"))
      (node (ref "U19") (pin "17") (pinfunction "AGND_17") (pintype "passive"))
      (node (ref "U19") (pin "18") (pinfunction "AGND_18") (pintype "passive"))
      (node (ref "U19") (pin "21") (pinfunction "AGND_21") (pintype "passive"))
      (node (ref "U19") (pin "24") (pinfunction "AGND_24") (pintype "passive"))
      (node (ref "U19") (pin "27") (pinfunction "AGND_27") (pintype "passive"))
      (node (ref "U19") (pin "28") (pinfunction "AGND_28") (pintype "passive"))
      (node (ref "U19") (pin "31") (pinfunction "AGND_31") (pintype "passive"))
      (node (ref "U19") (pin "32") (pinfunction "AGND_32") (pintype "passive"))
      (node (ref "U19") (pin "39") (pinfunction "DRGND_39") (pintype "passive"))
      (node (ref "U19") (pin "49") (pinfunction "DRGND_49") (pintype "passive"))
      (node (ref "U19") (pin "59") (pinfunction "DRGND_59") (pintype "passive"))
      (node (ref "U19") (pin "PAD") (pinfunction "DRGND_PAD") (pintype "passive"))
    )
    (net (code "49") (name "Net-(L10-Pad1)") (class "Default")
      (node (ref "L10") (pin "1") (pinfunction "1_1") (pintype "passive"))
      (node (ref "R97") (pin "2") (pinfunction "2_2") (pintype "passive"))
    )
    (net (code "50") (name "Net-(L11-Pad1)") (class "Default")
      (node (ref "L11") (pin "1") (pinfunction "1_1") (pintype "passive"))
      (node (ref "R99") (pin "2") (pinfunction "2_2") (pintype "passive"))
    )
    (net (code "51") (name "Net-(L12-Pad1)") (class "Default")
      (node (ref "L12") (pin "1") (pinfunction "1_1") (pintype "passive"))
      (node (ref "R103") (pin "2") (pinfunction "2_2") (pintype "passive"))
    )
    (net (code "52") (name "Net-(L13-Pad1)") (class "Default")
      (node (ref "L13") (pin "1") (pinfunction "1_1") (pintype "passive"))
      (node (ref "R106") (pin "2") (pinfunction "2_2") (pintype "passive"))
    )
    (net (code "53") (name "Net-(U19A-INM_A)") (class "Default")
      (node (ref "C207") (pin "1") (pinfunction "1_1") (pintype "passive"))
      (node (ref "L11") (pin "2") (pinfunction "2_2") (pintype "passive"))
      (node (ref "U19") (pin "30") (pinfunction "INM_A_30") (pintype "passive"))
    )
    (net (code "54") (name "Net-(U19A-INP_A)") (class "Default")
      (node (ref "C207") (pin "2") (pinfunction "2_2") (pintype "passive"))
      (node (ref "L10") (pin "2") (pinfunction "2_2") (pintype "passive"))
      (node (ref "U19") (pin "29") (pinfunction "INP_A_29") (pintype "passive"))
    )
    (net (code "55") (name "Net-(U19B-INM_B)") (class "Default")
      (node (ref "C209") (pin "1") (pinfunction "1_1") (pintype "passive"))
      (node (ref "L13") (pin "2") (pinfunction "2_2") (pintype "passive"))
      (node (ref "U19") (pin "20") (pinfunction "INM_B_20") (pintype "passive"))
    )
    (net (code "56") (name "Net-(U19B-INP_B)") (class "Default")
      (node (ref "C209") (pin "2") (pinfunction "2_2") (pintype "passive"))
      (node (ref "L12") (pin "2") (pinfunction "2_2") (pintype "passive"))
      (node (ref "U19") (pin "19") (pinfunction "INP_B_19") (pintype "passive"))
    )
    (net (code "57") (name "Net-(U19C-CLKM)") (class "Default")
      (node (ref "C206") (pin "2") (pinfunction "2_2") (pintype "passive"))
      (node (ref "U19") (pin "26") (pinfunction "CLKM_26") (pintype "passive"))
    )
    (net (code "58") (name "Net-(U19C-CLKP)") (class "Default")
      (node (ref "C205") (pin "2") (pinfunction "2_2") (pintype "passive"))
      (node (ref "U19") (pin "25") (pinfunction "CLKP_25") (pintype "passive"))
    )
    (net (code "59") (name "Net-(U20A-+FB1)") (class "Default")
      (node (ref "R98") (pin "1") (pinfunction "1_1") (pintype "passive"))
      (node (ref "U20") (pin "2") (pinfunction "+FB1_2") (pintype "passive"))
    )
    (net (code "60") (name "Net-(U20A-+IN1)") (class "Default")
      (node (ref "R92") (pin "2") (pinfunction "2_2") (pintype "passive"))
      (node (ref "R94") (pin "1") (pinfunction "1_1") (pintype "passive"))
      (node (ref "U20") (pin "24") (pinfunction "+IN1_24") (pintype "passive"))
    )
    (net (code "61") (name "Net-(U20A-+OUT1)") (class "Default")
      (node (ref "R99") (pin "1") (pinfunction "1_1") (pintype "passive"))
      (node (ref "U20") (pin "18") (pinfunction "+OUT1_18") (pintype "passive"))
    )
    (net (code "62") (name "Net-(U20A--FB1)") (class "Default")
      (node (ref "R92") (pin "1") (pinfunction "1_1") (pintype "passive"))
      (node (ref "U20") (pin "23") (pinfunction "-FB1_23") (pintype "passive"))
    )
    (net (code "63") (name "Net-(U20A--IN1)") (class "Default")
      (node (ref "R95") (pin "1") (pinfunction "1_1") (pintype "passive"))
      (node (ref "R98") (pin "2") (pinfunction "2_2") (pintype "passive"))
      (node (ref "U20") (pin "1") (pinfunction "-IN1_1") (pintype "passive"))
    )
    (net (code "64") (name "Net-(U20A--OUT1)") (class "Default")
      (node (ref "R97") (pin "1") (pinfunction "1_1") (pintype "passive"))
      (node (ref "U20") (pin "19") (pinfunction "-OUT1_19") (pintype "passive"))
    )
    (net (code "65") (name "Net-(U20B-+FB2)") (class "Default")
      (node (ref "R105") (pin "1") (pinfunction "1_1") (pintype "passive"))
      (node (ref "U20") (pin "8") (pinfunction "+FB2_8") (pintype "passive"))
    )
    (net (code "66") (name "Net-(U20B-+IN2)") (class "Default")
      (node (ref "R100") (pin "2") (pinfunction "2_2") (pintype "passive"))
      (node (ref "R101") (pin "1") (pinfunction "1_1") (pintype "passive"))
      (node (ref "U20") (pin "6") (pinfunction "+IN2_6") (pintype "passive"))
    )
    (net (code "67") (name "Net-(U20B-+OUT2)") (class "Default")
      (node (ref "R106") (pin "1") (pinfunction "1_1") (pintype "passive"))
      (node (ref "U20") (pin "12") (pinfunction "+OUT2_12") (pintype "passive"))
    )
    (net (code "68") (name "Net-(U20B--FB2)") (class "Default")
      (node (ref "R100") (pin "1") (pinfunction "1_1") (pintype "passive"))
      (node (ref "U20") (pin "5") (pinfunction "-FB2_5") (pintype "passive"))
    )
    (net (code "69") (name "Net-(U20B--IN2)") (class "Default")
      (node (ref "R102") (pin "1") (pinfunction "1_1") (pintype "passive"))
      (node (ref "R105") (pin "2") (pinfunction "2_2") (pintype "passive"))
      (node (ref "U20") (pin "7") (pinfunction "-IN2_7") (pintype "passive"))
    )
    (net (code "70") (name "Net-(U20B--OUT2)") (class "Default")
      (node (ref "R103") (pin "1") (pinfunction "1_1") (pintype "passive"))
      (node (ref "U20") (pin "13") (pinfunction "-OUT2_13") (pintype "passive"))
    )
    (net (code "71") (name "unconnected-(U19C-NC-Pad22)") (class "Default")
      (node (ref "U19") (pin "22") (pinfunction "NC_22") (pintype "passive"))
    )
  )
)
